# Sheet1_without_res_cap.net
KiCad netlist of a schematic drawn in Altium Designer
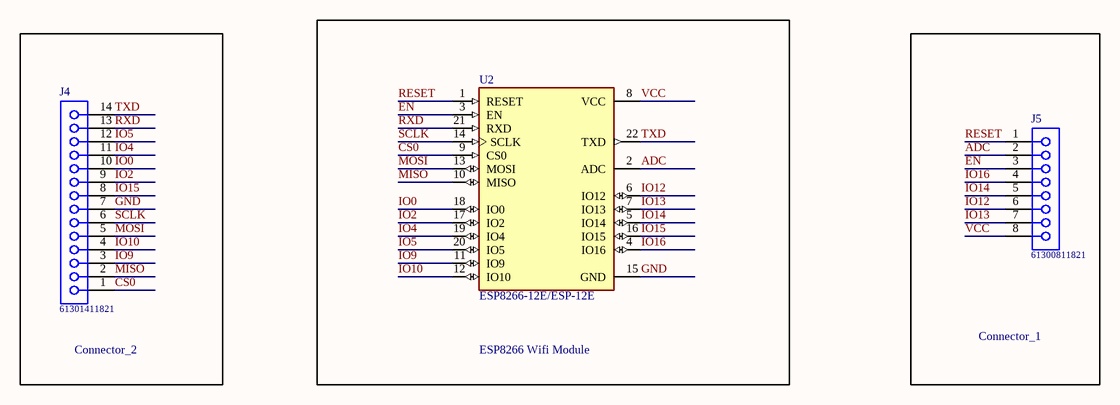
[diagram p0: Sheet1(without_res_cap).SchDoc]

(export (version "E")
  (design (tool "Eeschema 10.0.6"))
  (components
    (comp (ref "J4")
      (value "61301411821")
      (footprint "61301411821")
      (description "WR-PHD Socket Header, THT, pitch 2.54mm, Single Row, Vertical, 14p")
      (fields (field (name "MANUFACTURER") "Wurth Elektronik"))
      (libsource (lib "Altium_WR-PHD (rev20a) (2)") (part "61301411821"))
    )
    (comp (ref "J5")
      (value "61300811821")
      (footprint "61300811821")
      (description "WR-PHD Socket Header, THT, pitch 2.54mm, Single Row, Vertical, 8p")
      (fields (field (name "MANUFACTURER") "Wurth Elektronik"))
      (libsource (lib "Altium_WR-PHD (rev20a)") (part "61300811821"))
    )
    (comp (ref "U2")
      (value "ESP8266-12E/ESP-12E")
      (footprint "XCVR_ESP8266-12E/ESP-12E")
      (fields (field (name "MF") "AI-Thinker"))
      (libsource (lib "ESP8266-12E_ESP-12E") (part "ESP8266-12E/ESP-12E"))
    )
  )
  (nets
    (net (code "1") (name "/ADC") (class "Default")
      (node (ref "J5") (pin "2") (pinfunction "2_2") (pintype "passive"))
      (node (ref "U2") (pin "2") (pinfunction "ADC_2") (pintype "passive"))
    )
    (net (code "2") (name "/CS0") (class "Default")
      (node (ref "J4") (pin "1") (pinfunction "1_1") (pintype "passive"))
      (node (ref "U2") (pin "9") (pinfunction "CS0_9") (pintype "input"))
    )
    (net (code "3") (name "/EN") (class "Default")
      (node (ref "J5") (pin "3") (pinfunction "3_3") (pintype "passive"))
      (node (ref "U2") (pin "3") (pinfunction "EN_3") (pintype "input"))
    )
    (net (code "4") (name "/GND") (class "Default")
      (node (ref "J4") (pin "7") (pinfunction "7_7") (pintype "passive"))
      (node (ref "U2") (pin "15") (pinfunction "GND_15") (pintype "power_in"))
    )
    (net (code "5") (name "/IO0") (class "Default")
      (node (ref "J4") (pin "10") (pinfunction "10_10") (pintype "passive"))
      (node (ref "U2") (pin "18") (pinfunction "IO0_18") (pintype "bidirectional"))
    )
    (net (code "6") (name "/IO2") (class "Default")
      (node (ref "J4") (pin "9") (pinfunction "9_9") (pintype "passive"))
      (node (ref "U2") (pin "17") (pinfunction "IO2_17") (pintype "bidirectional"))
    )
    (net (code "7") (name "/IO4") (class "Default")
      (node (ref "J4") (pin "11") (pinfunction "11_11") (pintype "passive"))
      (node (ref "U2") (pin "19") (pinfunction "IO4_19") (pintype "bidirectional"))
    )
    (net (code "8") (name "/IO5") (class "Default")
      (node (ref "J4") (pin "12") (pinfunction "12_12") (pintype "passive"))
      (node (ref "U2") (pin "20") (pinfunction "IO5_20") (pintype "bidirectional"))
    )
    (net (code "9") (name "/IO9") (class "Default")
      (node (ref "J4") (pin "3") (pinfunction "3_3") (pintype "passive"))
      (node (ref "U2") (pin "11") (pinfunction "IO9_11") (pintype "bidirectional"))
    )
    (net (code "10") (name "/IO10") (class "Default")
      (node (ref "J4") (pin "4") (pinfunction "4_4") (pintype "passive"))
      (node (ref "U2") (pin "12") (pinfunction "IO10_12") (pintype "bidirectional"))
    )
    (net (code "11") (name "/IO12") (class "Default")
      (node (ref "J5") (pin "6") (pinfunction "6_6") (pintype "passive"))
      (node (ref "U2") (pin "6") (pinfunction "IO12_6") (pintype "bidirectional"))
    )
    (net (code "12") (name "/IO13") (class "Default")
      (node (ref "J5") (pin "7") (pinfunction "7_7") (pintype "passive"))
      (node (ref "U2") (pin "7") (pinfunction "IO13_7") (pintype "bidirectional"))
    )
    (net (code "13") (name "/IO14") (class "Default")
      (node (ref "J5") (pin "5") (pinfunction "5_5") (pintype "passive"))
      (node (ref "U2") (pin "5") (pinfunction "IO14_5") (pintype "bidirectional"))
    )
    (net (code "14") (name "/IO15") (class "Default")
      (node (ref "J4") (pin "8") (pinfunction "8_8") (pintype "passive"))
      (node (ref "U2") (pin "16") (pinfunction "IO15_16") (pintype "bidirectional"))
    )
    (net (code "15") (name "/IO16") (class "Default")
      (node (ref "J5") (pin "4") (pinfunction "4_4") (pintype "passive"))
      (node (ref "U2") (pin "4") (pinfunction "IO16_4") (pintype "bidirectional"))
    )
    (net (code "16") (name "/MISO") (class "Default")
      (node (ref "J4") (pin "2") (pinfunction "2_2") (pintype "passive"))
      (node (ref "U2") (pin "10") (pinfunction "MISO_10") (pintype "bidirectional"))
    )
    (net (code "17") (name "/MOSI") (class "Default")
      (node (ref "J4") (pin "5") (pinfunction "5_5") (pintype "passive"))
      (node (ref "U2") (pin "13") (pinfunction "MOSI_13") (pintype "bidirectional"))
    )
    (net (code "18") (name "/RESET") (class "Default")
      (node (ref "J5") (pin "1") (pinfunction "1_1") (pintype "passive"))
      (node (ref "U2") (pin "1") (pinfunction "RESET_1") (pintype "input"))
    )
    (net (code "19") (name "/RXD") (class "Default")
      (node (ref "J4") (pin "13") (pinfunction "13_13") (pintype "passive"))
      (node (ref "U2") (pin "21") (pinfunction "RXD_21") (pintype "input"))
    )
    (net (code "20") (name "/SCLK") (class "Default")
      (node (ref "J4") (pin "6") (pinfunction "6_6") (pintype "passive"))
      (node (ref "U2") (pin "14") (pinfunction "SCLK_14") (pintype "input"))
    )
    (net (code "21") (name "/TXD") (class "Default")
      (node (ref "J4") (pin "14") (pinfunction "14_14") (pintype "passive"))
      (node (ref "U2") (pin "22") (pinfunction "TXD_22") (pintype "output"))
    )
    (net (code "22") (name "/VCC") (class "Default")
      (node (ref "J5") (pin "8") (pinfunction "8_8") (pintype "passive"))
      (node (ref "U2") (pin "8") (pinfunction "VCC_8") (pintype "power_in"))
    )
  )
)
